# JacdacRgbLedGeneric_60.net
KiCad netlist of a schematic drawn in Altium Designer
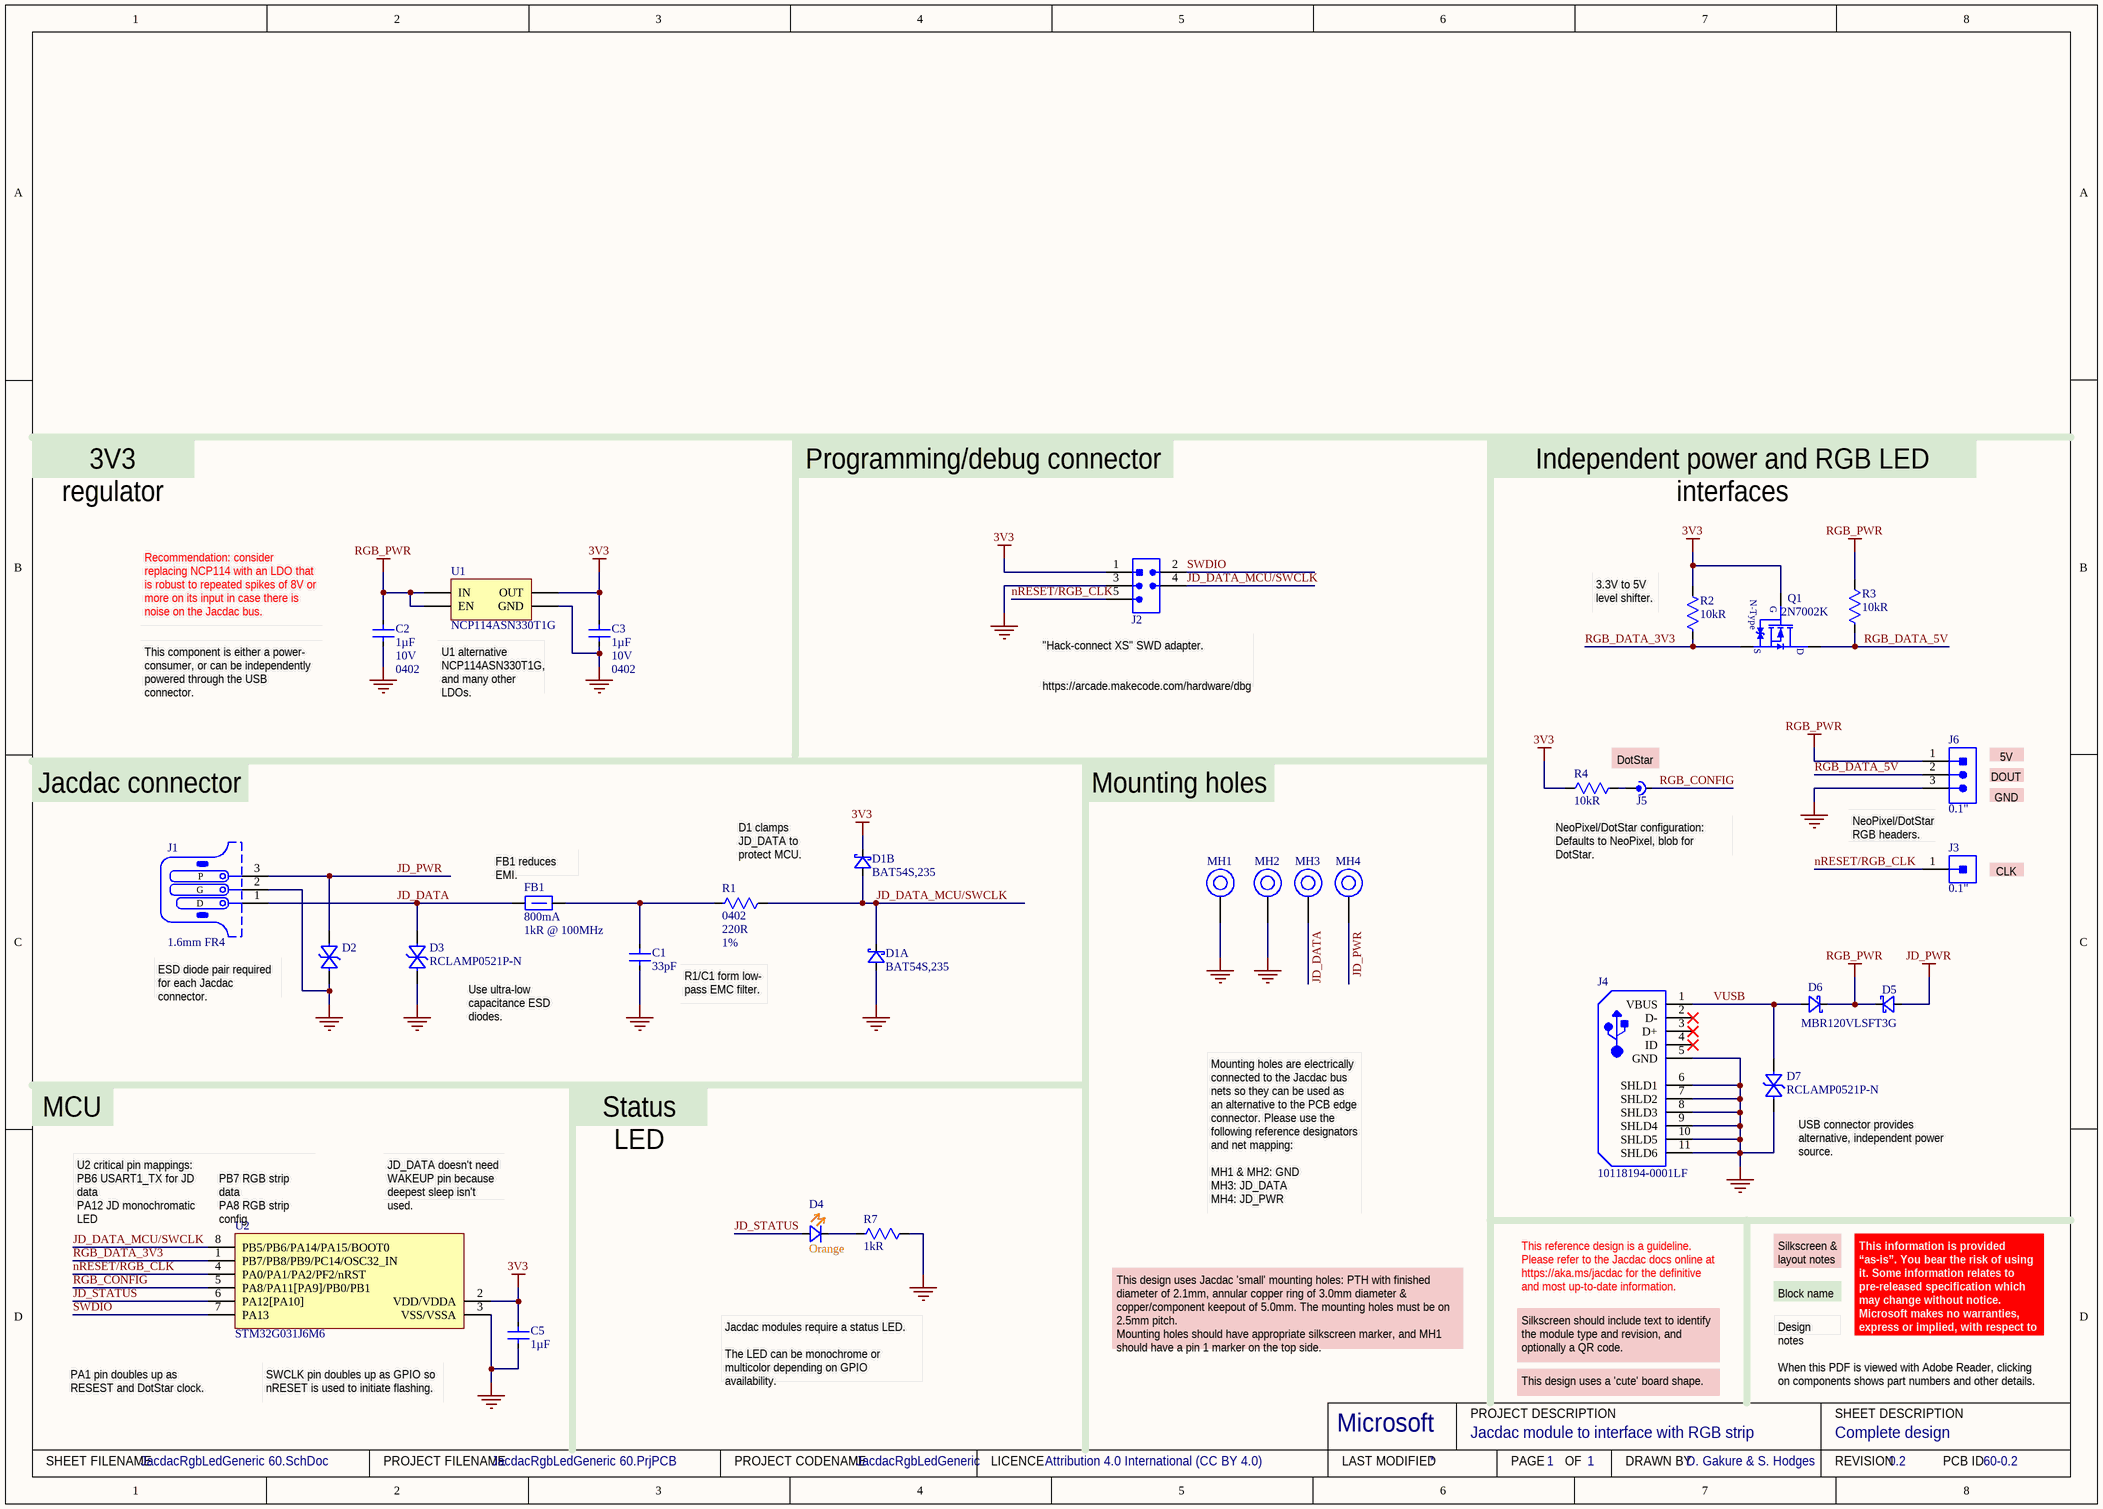
[diagram p0: JacdacRgbLedGeneric 60.SchDoc]

(export (version "E")
  (design (tool "Eeschema 10.0.6"))
  (components
    (comp (ref "C1")
      (value "CL05C330JB51PNC")
      (footprint "C0402_0.55MM - without outline")
      (description "CAP CER 33PF 50V NP0 0402")
      (fields
        (field (name "MANUFACTURER") "Samsung")
        (field (name "TOLERANCE") "5%")
        (field (name "CAPACITANCE") "33pF")
        (field (name "CHECKED") "?")
        (field (name "CREATED") "DG")
      )
      (libsource (lib "Samsung") (part "CL05C330JB51PNC"))
    )
    (comp (ref "C2")
      (value "CL05A105KP5NNNC")
      (footprint "C0402_0.55MM - without outline")
      (description "CAP CER 1UF 10V X5R 0402")
      (fields
        (field (name "MANUFACTURER") "Samsung")
        (field (name "TOLERANCE") "10%")
        (field (name "CAPACITANCE") "1µF")
        (field (name "VOLTAGE RATING") "10V")
        (field (name "CASE CODE (IMPERIAL)") "0402")
        (field (name "CREATED") "DG")
        (field (name "CHECKED") "?")
      )
      (libsource (lib "Samsung") (part "CL05A105KP5NNNC"))
    )
    (comp (ref "C3")
      (value "CL05A105KP5NNNC")
      (footprint "C0402_0.55MM - without outline")
      (description "CAP CER 1UF 10V X5R 0402")
      (fields
        (field (name "MANUFACTURER") "Samsung")
        (field (name "TOLERANCE") "10%")
        (field (name "CAPACITANCE") "1µF")
        (field (name "VOLTAGE RATING") "10V")
        (field (name "CASE CODE (IMPERIAL)") "0402")
        (field (name "CREATED") "DG")
        (field (name "CHECKED") "?")
      )
      (libsource (lib "Samsung") (part "CL05A105KP5NNNC"))
    )
    (comp (ref "C5")
      (value "CL05A105KP5NNNC")
      (footprint "C0402_0.55MM - without outline")
      (description "CAP CER 1UF 10V X5R 0402")
      (fields
        (field (name "MANUFACTURER") "Samsung")
        (field (name "TOLERANCE") "10%")
        (field (name "CAPACITANCE") "1µF")
        (field (name "CREATED") "DG")
        (field (name "CHECKED") "?")
      )
      (libsource (lib "Samsung") (part "CL05A105KP5NNNC"))
    )
    (comp (ref "D1")
      (value "BAT54S")
      (footprint "NXP-BAT54S-TO-236AB - without outline")
      (description "DIODE ARRAY SCHOTTKY 30V SOT23")
      (fields (field (name "MANUFACTURER") "Nexperia") (field (name "MANUFACTURER PART NUMBER") "BAT54S,235"))
      (libsource (lib "NXP") (part "BAT54S"))
    )
    (comp (ref "D2")
      (value "RCLAMP0521P-N")
      (footprint "TVS 0402 - L")
      (description "Bidirectional 5V (Max) 6V 16V 3.5A (8/20us) 0402 TVS RoHS")
      (fields
        (field (name "MANUFACTURER") "Born Semiconductor")
        (field (name "CREATED BY") "D Gakure")
        (field (name "CHECKED BY") "?")
      )
      (libsource (lib "BornSemiconductor") (part "RCLAMP0521P-N"))
    )
    (comp (ref "D3")
      (value "RCLAMP0521P-N")
      (footprint "TVS 0402 - L")
      (description "Bidirectional 5V (Max) 6V 16V 3.5A (8/20us) 0402 TVS RoHS")
      (fields
        (field (name "MANUFACTURER") "Born Semiconductor")
        (field (name "MANUFACTURER PART NUMBER") "RCLAMP0521P-N")
        (field (name "CREATED BY") "D Gakure")
        (field (name "CHECKED BY") "?")
      )
      (libsource (lib "BornSemiconductor") (part "RCLAMP0521P-N"))
    )
    (comp (ref "D4")
      (value "SML-D12D")
      (footprint "Rohm SML-D12 Orange - without outline")
      (description "1.6 x 0.8 x 0.55mm (0603) LED 605nm Orange")
      (fields
        (field (name "MANUFACTURER") "Rohm Semiconductor")
        (field (name "MANUFACTURER PART NUMBER") "SML-D12D8WT86")
        (field (name "COLOUR") "Orange")
      )
      (libsource (lib "Rohm") (part "SML-D12D"))
    )
    (comp (ref "D5")
      (value "MBR120VLSFT3G")
      (footprint "MBR120VLSFT3G")
      (description "DIODE SCHOTTKY 20V 1A SOD123FL")
      (fields (field (name "MANUFACTURER") "ON Semiconductor"))
      (libsource (lib "OnSemiconductor") (part "MBR120VLSFT3G"))
    )
    (comp (ref "D6")
      (value "MBR120VLSFT3G")
      (footprint "MBR120VLSFT3G")
      (description "DIODE SCHOTTKY 20V 1A SOD123FL")
      (fields
        (field (name "MANUFACTURER") "ON Semiconductor")
        (field (name "MANUFACTURER PART NUMBER") "MBR120VLSFT3G")
      )
      (libsource (lib "OnSemiconductor") (part "MBR120VLSFT3G"))
    )
    (comp (ref "D7")
      (value "RCLAMP0521P-N")
      (footprint "TVS 0402 - L")
      (description "Bidirectional 5V (Max) 6V 16V 3.5A (8/20us) 0402 TVS RoHS")
      (fields
        (field (name "MANUFACTURER") "Born Semiconductor")
        (field (name "MANUFACTURER PART NUMBER") "RCLAMP0521P-N")
        (field (name "CREATED BY") "D Gakure")
        (field (name "CHECKED BY") "?")
      )
      (libsource (lib "BornSemiconductor") (part "RCLAMP0521P-N"))
    )
    (comp (ref "FB1")
      (value "TDK MPZ1608S102ATA00")
      (footprint "TDK MPZ1608 0.8mm - without outline")
      (description "0603 1k@100MHz 0.8A chip")
      (fields
        (field (name "TOLERANCE") "25%")
        (field (name "MANUFACTURER") "TDK")
        (field (name "CURRENT RATING") "800mA")
        (field (name "IMPEDANCE") "1kR @ 100MHz")
      )
      (libsource (lib "TDK") (part "TDK MPZ1608S102ATA00"))
    )
    (comp (ref "J1")
      (value "3 pin JACDAC edge connector")
      (footprint "JACDAC_EDGE_CONNECTOR_NO_TRACES")
      (description "3 pin JACDAC edge connector 1.27mm pitch")
      (fields
        (field (name "MANUFACTURER PART NUMBER") "JACDAC_EDGE_CONNECTOR")
        (field (name "PCB TYPE") "1.6mm FR4")
        (field (name "CHECKED BY") "?")
        (field (name "CREATED BY") "D. Gakure")
      )
      (libsource (lib "generic-con") (part "Jacdac edge connector"))
    )
    (comp (ref "J2")
      (value "Hack Connect Mini 1.27 mm pitch 2-row")
      (footprint "HACK_CONNECT_MINI_5_X_1_27")
      (libsource (lib "HackConnect") (part "HACK_CONNECT_MINI"))
    )
    (comp (ref "J3")
      (value "0.1\"")
      (footprint "Generic 1x1 2.54mm header -with SMD pads")
      (description "2.54mm, 1x1 way")
      (libsource (lib "generic-con") (part "Generic Header 2.54mm, 1x1 way."))
    )
    (comp (ref "J4")
      (value "Amphenol FCI 10118194-0001LF")
      (footprint "FCI-10118194-0001LF-5_V no slots")
      (description "CONN USB MICRO B RECPT SMT R/A")
      (fields
        (field (name "MANUFACTURER") "Amphenol FCI")
        (field (name "MANUFACTURER PART NUMBER") "10118194-0001LF")
        (field (name "CREATED BY") "HUGHWI")
      )
      (libsource (lib "Amphenol") (part "Amphenol FCI 10118194-0001LF"))
    )
    (comp (ref "J5")
      (value "OpenSolderBlob")
      (footprint "SolderBlobA")
      (description "Open solder blob")
      (libsource (lib "generic") (part "OpenSolderBlob"))
    )
    (comp (ref "J6")
      (value "0.1\"")
      (footprint "Generic 1x3 2.54mm header -with SMD pads")
      (description "2.54mm, 3x1 way")
      (libsource (lib "generic-con") (part "Generic Header 2.54mm, 3x1 way."))
    )
    (comp (ref "MH1")
      (value "MH_5.0MMK_3.0MMC_2.1MMD_PTH")
      (footprint "MH_5.0MMK_3.0MMC_2.1MMD_PTH:MH_5.0MMK_3.0MMC_2.1MMD_PTH")
      (description "Mounting Hole 5.0mm keepout, 3.0mm annualar ring and 2.1mm Drill PTH")
      (libsource (lib "generic") (part "MH_5.0MMK_3.0MMC_2.1MMD_PTH"))
    )
    (comp (ref "MH2")
      (value "MH_5.0MMK_3.0MMC_2.1MMD_PTH")
      (footprint "MH_5.0MMK_3.0MMC_2.1MMD_PTH:MH_5.0MMK_3.0MMC_2.1MMD_PTH")
      (description "Mounting Hole 5.0mm keepout, 3.0mm annualar ring and 2.1mm Drill PTH")
      (libsource (lib "generic") (part "MH_5.0MMK_3.0MMC_2.1MMD_PTH"))
    )
    (comp (ref "MH3")
      (value "MH_5.0MMK_3.0MMC_2.1MMD_PTH")
      (footprint "MH_5.0MMK_3.0MMC_2.1MMD_PTH:MH_5.0MMK_3.0MMC_2.1MMD_PTH")
      (description "Mounting Hole 5.0mm keepout, 3.0mm annualar ring and 2.1mm Drill PTH")
      (libsource (lib "generic") (part "MH_5.0MMK_3.0MMC_2.1MMD_PTH"))
    )
    (comp (ref "MH4")
      (value "MH_5.0MMK_3.0MMC_2.1MMD_PTH")
      (footprint "MH_5.0MMK_3.0MMC_2.1MMD_PTH")
      (description "Mounting Hole 5.0mm keepout, 3.0mm annualar ring and 2.1mm Drill PTH")
      (libsource (lib "generic") (part "MH_5.0MMK_3.0MMC_2.1MMD_PTH"))
    )
    (comp (ref "Q1")
      (value "2N7002K")
      (footprint "SOT-23")
      (description "MOSFET Transistor, N Channel, 300 mA, 60 V, 2 ohm, 10 V, 2.5 V")
      (fields
        (field (name "MANUFACTURER") "ON Semiconductor / Fairchild")
        (field (name "VOLTAGE") "60V")
        (field (name "MANUFACTURER PART NUMBER") "2N7002K")
        (field (name "CREATED BY") "D. Gakure")
        (field (name "CHECKED BY") "?")
      )
      (libsource (lib "OnSemiconductor") (part "2N7002K (2)"))
    )
    (comp (ref "R1")
      (value "RC0402FR-07220RL")
      (footprint "R0402 - Without outline")
      (description "RES SMD 220 OHM 1% 1/16W 0402")
      (fields
        (field (name "MANUFACTURER") "Yageo")
        (field (name "CASE CODE (IMPERIAL)") "0402")
        (field (name "RESISTANCE") "220R")
        (field (name "TOLERANCE") "1%")
        (field (name "CREATED") "D.G")
        (field (name "CHECKED") "?")
      )
      (libsource (lib "Yageo") (part "RC0402FR-07220RL"))
    )
    (comp (ref "R2")
      (value "10k")
      (footprint "R0402 - Without outline")
      (description "RES SMD 10K OHM 1% 1/16W 0402")
      (fields
        (field (name "MANUFACTURER") "Yageo")
        (field (name "MANUFACTURER PART NUMBER") "RC0402FR-0710KL")
        (field (name "RESISTANCE") "10kR")
        (field (name "CHECKED") "?")
        (field (name "CREATED") "DG")
      )
      (libsource (lib "Yageo") (part "RC0402FR-0710KL"))
    )
    (comp (ref "R3")
      (value "10k")
      (footprint "R0402 - Without outline")
      (description "RES SMD 10K OHM 1% 1/16W 0402")
      (fields
        (field (name "MANUFACTURER") "Yageo")
        (field (name "MANUFACTURER PART NUMBER") "RC0402FR-0710KL")
        (field (name "RESISTANCE") "10kR")
        (field (name "CHECKED") "?")
        (field (name "CREATED") "DG")
      )
      (libsource (lib "Yageo") (part "RC0402FR-0710KL"))
    )
    (comp (ref "R4")
      (value "10k")
      (footprint "R0402 - Without outline")
      (description "RES SMD 10K OHM 1% 1/16W 0402")
      (fields
        (field (name "MANUFACTURER") "Yageo")
        (field (name "MANUFACTURER PART NUMBER") "RC0402FR-0710KL")
        (field (name "RESISTANCE") "10kR")
        (field (name "CHECKED") "?")
        (field (name "CREATED") "DG")
      )
      (libsource (lib "Yageo") (part "RC0402FR-0710KL"))
    )
    (comp (ref "R7")
      (value "RC0402FR-071KL")
      (footprint "R0402 - Without outline")
      (description "RES SMD 1K OHM 1% 1/16W 0402")
      (fields
        (field (name "MANUFACTURER") "Yageo")
        (field (name "TOLERANCE") "1%")
        (field (name "RESISTANCE") "1kR")
        (field (name "CREATED") "D.G")
        (field (name "CHECKED") "?")
      )
      (libsource (lib "Yageo") (part "RC0402FR-071KL"))
    )
    (comp (ref "U1")
      (value "LDO 3.3V/300 mA")
      (footprint "ON_SEMI-SOT23-5 - without outline")
      (fields
        (field (name "MANUFACTURER") "ON Semiconductor")
        (field (name "MANUFACTURER PART NUMBER") "NCP114ASN330T1G")
        (field (name "CREATED") "DG")
        (field (name "CHECKED") "?")
      )
      (libsource (lib "OnSemiconductor") (part "NCP114ASN330T1G"))
    )
    (comp (ref "U2")
      (value "STM32G031J6M6")
      (footprint "8-SOIC")
      (description "MCU 32-bit ARM Cortex M0+ RISC 32KB Flash 2.5V/3.3V 8-Pin SO N Tube")
      (fields
        (field (name "MANUFACTURER") "STMicroelectronics")
        (field (name "MANUFACTURER PART NUMBER") "STM32G031J6M6")
        (field (name "CREATED BY") "D. Gakure")
        (field (name "CHECKED BY") "?")
      )
      (libsource (lib "ST") (part "STM32G031J6M6"))
    )
  )
  (nets
    (net (code "1") (name "/JD_DATA") (class "Default")
      (node (ref "D3") (pin "1") (pinfunction "K_1") (pintype "passive"))
      (node (ref "FB1") (pin "1") (pinfunction "1_1") (pintype "passive"))
      (node (ref "J1") (pin "1") (pinfunction "D_1") (pintype "passive"))
      (node (ref "MH3") (pin "1") (pinfunction "1_1") (pintype "passive"))
    )
    (net (code "2") (name "/JD_DATA_MCU{slash}SWCLK") (class "Default")
      (node (ref "D1") (pin "3") (pinfunction "K_3") (pintype "passive"))
      (node (ref "J2") (pin "4") (pinfunction "SWCLK_4") (pintype "passive"))
      (node (ref "R1") (pin "1") (pinfunction "1_1") (pintype "passive"))
      (node (ref "U2") (pin "8") (pinfunction "PB5/PB6/PA14/PA15/BOOT0_8") (pintype "passive"))
    )
    (net (code "3") (name "/JD_STATUS") (class "Default")
      (node (ref "D4") (pin "2") (pinfunction "A_2") (pintype "passive"))
      (node (ref "U2") (pin "6") (pinfunction "PA12[PA10]_6") (pintype "passive"))
    )
    (net (code "4") (name "/RGB_CONFIG") (class "Default")
      (node (ref "J5") (pin "2") (pinfunction "2_2") (pintype "passive"))
      (node (ref "U2") (pin "5") (pinfunction "PA8/PA11[PA9]/PB0/PB1_5") (pintype "passive"))
    )
    (net (code "5") (name "/RGB_DATA_3V3") (class "Default")
      (node (ref "Q1") (pin "2") (pinfunction "S_2") (pintype "passive"))
      (node (ref "R2") (pin "2") (pinfunction "2_2") (pintype "passive"))
      (node (ref "U2") (pin "1") (pinfunction "PB7/PB8/PB9/PC14/OSC32_IN_1") (pintype "passive"))
    )
    (net (code "6") (name "/RGB_DATA_5V") (class "Default")
      (node (ref "J6") (pin "2") (pinfunction "2_2") (pintype "passive"))
      (node (ref "Q1") (pin "3") (pinfunction "D_3") (pintype "passive"))
      (node (ref "R3") (pin "2") (pinfunction "2_2") (pintype "passive"))
    )
    (net (code "7") (name "/SWDIO") (class "Default")
      (node (ref "J2") (pin "2") (pinfunction "SWDIO_2") (pintype "passive"))
      (node (ref "U2") (pin "7") (pinfunction "PA13_7") (pintype "passive"))
    )
    (net (code "8") (name "/VUSB") (class "Default")
      (node (ref "D6") (pin "2") (pinfunction "A_2") (pintype "passive"))
      (node (ref "D7") (pin "1") (pinfunction "K_1") (pintype "passive"))
      (node (ref "J4") (pin "1") (pinfunction "VBUS_1") (pintype "passive"))
    )
    (net (code "9") (name "/nRESET{slash}RGB_CLK") (class "Default")
      (node (ref "J2") (pin "5") (pinfunction "RESET_5") (pintype "passive"))
      (node (ref "J3") (pin "1") (pinfunction "1_1") (pintype "passive"))
      (node (ref "U2") (pin "4") (pinfunction "PA0/PA1/PA2/PF2/nRST_4") (pintype "passive"))
    )
    (net (code "10") (name "3V3") (class "Default")
      (node (ref "C3") (pin "2") (pinfunction "2_2") (pintype "passive"))
      (node (ref "C5") (pin "2") (pinfunction "2_2") (pintype "passive"))
      (node (ref "D1") (pin "2") (pinfunction "K_2") (pintype "passive"))
      (node (ref "J2") (pin "1") (pinfunction "VCC_1") (pintype "passive"))
      (node (ref "Q1") (pin "1") (pinfunction "G_1") (pintype "passive"))
      (node (ref "R2") (pin "1") (pinfunction "1_1") (pintype "passive"))
      (node (ref "R4") (pin "1") (pinfunction "1_1") (pintype "passive"))
      (node (ref "U1") (pin "5") (pinfunction "OUT_5") (pintype "passive"))
      (node (ref "U2") (pin "2") (pinfunction "VDD/VDDA_2") (pintype "passive"))
    )
    (net (code "11") (name "GND") (class "Default")
      (node (ref "C1") (pin "1") (pinfunction "1_1") (pintype "passive"))
      (node (ref "C2") (pin "1") (pinfunction "1_1") (pintype "passive"))
      (node (ref "C3") (pin "1") (pinfunction "1_1") (pintype "passive"))
      (node (ref "C5") (pin "1") (pinfunction "1_1") (pintype "passive"))
      (node (ref "D1") (pin "1") (pinfunction "A_1") (pintype "passive"))
      (node (ref "D2") (pin "2") (pinfunction "A_2") (pintype "passive"))
      (node (ref "D3") (pin "2") (pinfunction "A_2") (pintype "passive"))
      (node (ref "D7") (pin "2") (pinfunction "A_2") (pintype "passive"))
      (node (ref "J1") (pin "2") (pinfunction "G_2") (pintype "passive"))
      (node (ref "J2") (pin "3") (pinfunction "GND_3") (pintype "passive"))
      (node (ref "J4") (pin "10") (pinfunction "SHLD5_10") (pintype "passive"))
      (node (ref "J4") (pin "11") (pinfunction "SHLD6_11") (pintype "passive"))
      (node (ref "J4") (pin "5") (pinfunction "GND_5") (pintype "passive"))
      (node (ref "J4") (pin "6") (pinfunction "SHLD1_6") (pintype "passive"))
      (node (ref "J4") (pin "7") (pinfunction "SHLD2_7") (pintype "passive"))
      (node (ref "J4") (pin "8") (pinfunction "SHLD3_8") (pintype "passive"))
      (node (ref "J4") (pin "9") (pinfunction "SHLD4_9") (pintype "passive"))
      (node (ref "J6") (pin "3") (pinfunction "3_3") (pintype "passive"))
      (node (ref "MH1") (pin "1") (pinfunction "1_1") (pintype "passive"))
      (node (ref "MH2") (pin "1") (pinfunction "1_1") (pintype "passive"))
      (node (ref "R7") (pin "1") (pinfunction "1_1") (pintype "passive"))
      (node (ref "U1") (pin "2") (pinfunction "GND_2") (pintype "passive"))
      (node (ref "U2") (pin "3") (pinfunction "VSS/VSSA_3") (pintype "passive"))
    )
    (net (code "12") (name "JD_PWR") (class "Default")
      (node (ref "D2") (pin "1") (pinfunction "K_1") (pintype "passive"))
      (node (ref "D5") (pin "2") (pinfunction "A_2") (pintype "passive"))
      (node (ref "J1") (pin "3") (pinfunction "P_3") (pintype "passive"))
      (node (ref "MH4") (pin "1") (pinfunction "1_1") (pintype "passive"))
    )
    (net (code "13") (name "Net-(C1-Pad2)") (class "Default")
      (node (ref "C1") (pin "2") (pinfunction "2_2") (pintype "passive"))
      (node (ref "FB1") (pin "2") (pinfunction "2_2") (pintype "passive"))
      (node (ref "R1") (pin "2") (pinfunction "2_2") (pintype "passive"))
    )
    (net (code "14") (name "Net-(D4-K)") (class "Default")
      (node (ref "D4") (pin "1") (pinfunction "K_1") (pintype "passive"))
      (node (ref "R7") (pin "2") (pinfunction "2_2") (pintype "passive"))
    )
    (net (code "15") (name "Net-(J5-Pad1)") (class "Default")
      (node (ref "J5") (pin "1") (pinfunction "1_1") (pintype "passive"))
      (node (ref "R4") (pin "2") (pinfunction "2_2") (pintype "passive"))
    )
    (net (code "16") (name "RGB_PWR") (class "Default")
      (node (ref "C2") (pin "2") (pinfunction "2_2") (pintype "passive"))
      (node (ref "D5") (pin "1") (pinfunction "K_1") (pintype "passive"))
      (node (ref "D6") (pin "1") (pinfunction "K_1") (pintype "passive"))
      (node (ref "J6") (pin "1") (pinfunction "1_1") (pintype "passive"))
      (node (ref "R3") (pin "1") (pinfunction "1_1") (pintype "passive"))
      (node (ref "U1") (pin "1") (pinfunction "IN_1") (pintype "passive"))
      (node (ref "U1") (pin "3") (pinfunction "EN_3") (pintype "passive"))
    )
    (net (code "17") (name "unconnected-(J4-D+-Pad3)") (class "Default")
      (node (ref "J4") (pin "3") (pinfunction "D+_3") (pintype "passive+no_connect"))
    )
    (net (code "18") (name "unconnected-(J4-D--Pad2)") (class "Default")
      (node (ref "J4") (pin "2") (pinfunction "D-_2") (pintype "passive+no_connect"))
    )
    (net (code "19") (name "unconnected-(J4-ID-Pad4)") (class "Default")
      (node (ref "J4") (pin "4") (pinfunction "ID_4") (pintype "passive+no_connect"))
    )
  )
)
